# POWER_Management.net
KiCad netlist of a schematic drawn in Altium Designer
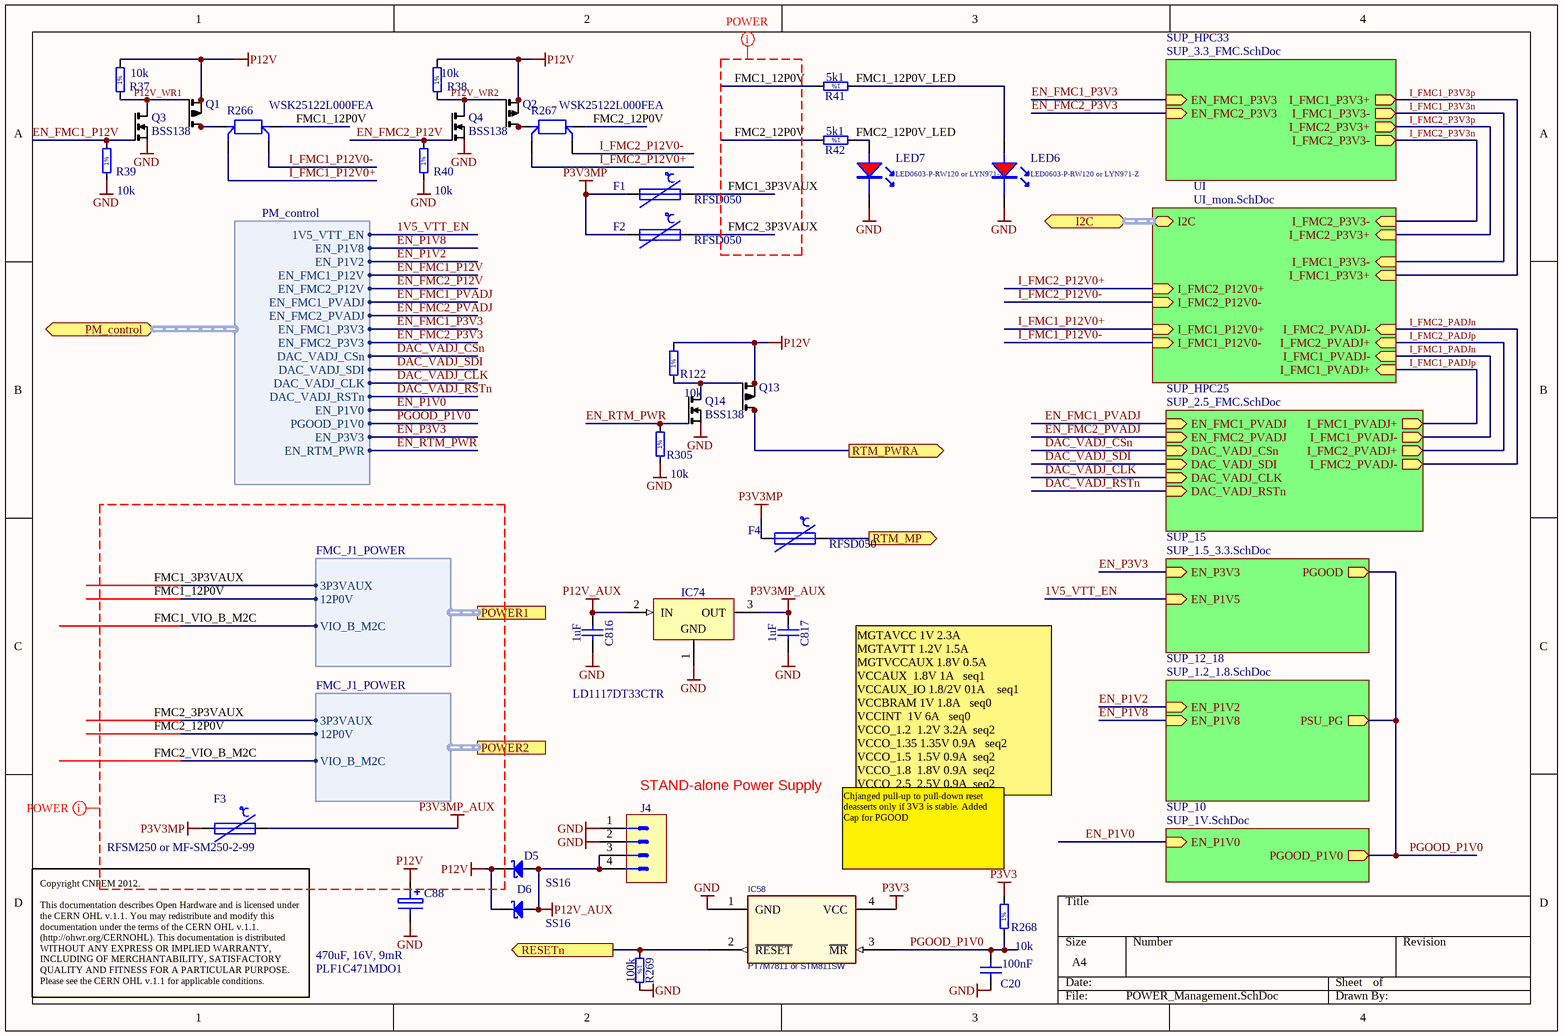
[diagram p0: POWER_Management.SchDoc]

(export (version "E")
  (design (tool "Eeschema 10.0.6"))
  (components
    (comp (ref "C20")
      (value "100nF")
      (footprint "CAPC0603X33N")
      (description "Non-polarised capacitor")
      (fields
        (field (name "PART NUMBER") "CC0201_100NF_6.3V_10%_X5R")
        (field (name "VOLTAGE") "6.3V")
        (field (name "AUTHOR") "CERN DEM JLC")
      )
      (libsource (lib "Capacitors") (part "Capacitor - non polarized"))
    )
    (comp (ref "C88")
      (value "PLF1C471MDO1")
      (footprint "CAPPR500-1000X1250")
      (description "POLY, 470uF, 16V, ESR: 9mR")
      (fields (field (name "ALTIUM_VALUE") "470uF, 16V, 9mR"))
      (libsource (lib "LIBRARY_SCH") (part "CAP_POLYMER_10mm"))
    )
    (comp (ref "C816")
      (value "1uF")
      (footprint "CAPC1608X87N")
      (description "Non-polarised capacitor")
      (fields
        (field (name "PART NUMBER") "CC0603_1UF_16V_10%_X7R")
        (field (name "VOLTAGE") "16V")
        (field (name "AUTHOR") "CERN DEM JLC")
      )
      (libsource (lib "Capacitors") (part "Capacitor - non polarized"))
    )
    (comp (ref "C817")
      (value "1uF")
      (footprint "CAPC1608X87N")
      (description "Non-polarised capacitor")
      (fields
        (field (name "PART NUMBER") "CC0603_1UF_16V_10%_X7R")
        (field (name "VOLTAGE") "16V")
        (field (name "AUTHOR") "CERN DEM JLC")
      )
      (libsource (lib "Capacitors") (part "Capacitor - non polarized"))
    )
    (comp (ref "D5")
      (value "SS16")
      (footprint "DIOM5127X229N")
      (description "Schottky Diode")
      (fields
        (field (name "VOLTAGE") "60V")
        (field (name "POWER") "1A")
        (field (name "AUTHOR") "CERN DEM JLC")
      )
      (libsource (lib "ICs And Semiconductors") (part "Diode Schottky"))
    )
    (comp (ref "D6")
      (value "SS16")
      (footprint "DIOM5127X229N")
      (description "Schottky Diode")
      (fields
        (field (name "VOLTAGE") "60V")
        (field (name "POWER") "1A")
        (field (name "AUTHOR") "CERN DEM JLC")
      )
      (libsource (lib "ICs And Semiconductors") (part "Diode Schottky"))
    )
    (comp (ref "F1")
      (value "RFSD050")
      (footprint "PTC_SMD_1812")
      (description "0.50A/15V")
      (libsource (lib "LIBRARY_SCH") (part "F_PTC_1812"))
    )
    (comp (ref "F2")
      (value "RFSD050")
      (footprint "PTC_SMD_1812")
      (description "0.50A/15V")
      (libsource (lib "LIBRARY_SCH") (part "F_PTC_1812"))
    )
    (comp (ref "F3")
      (value "RFSM250 or MF-SM250-2-99")
      (footprint "SMD150-2")
      (description "2.50A/15V")
      (libsource (lib "LIBRARY_SCH") (part "F_PTC_9.5x6mm"))
    )
    (comp (ref "F4")
      (value "RFSD050")
      (footprint "PTC_SMD_1812")
      (description "0.50A/15V")
      (libsource (lib "LIBRARY_SCH") (part "F_PTC_1812"))
    )
    (comp (ref "IC58")
      (value "PT7M7811 or STM811SW")
      (footprint "SOT143B")
      (description "voltage supervisor")
      (libsource (lib "LIBRARY_SCH") (part "VOLT_STM811"))
    )
    (comp (ref "IC74")
      (value "LD1117DT33CTR")
      (footprint "TO228P972X240-3N-R540X510")
      (description "3-Terminal Regulator 1=GND 2=IN 3=OUT")
      (fields (field (name "MANUFACTURER") "ST MICROELECTRONICS") (field (name "AUTHOR") "CERN DEM JLC"))
      (libsource (lib "ICs And Semiconductors") (part "REG3 1GND-2IN-3OUT"))
    )
    (comp (ref "J4")
      (value "Mini-Fit Jr.™")
      (footprint "MOLEX_39-28-1043")
      (description "Connector 4 Male")
      (fields
        (field (name "PART NUMBER") "MOLEX_39-28-1043")
        (field (name "MANUFACTURER") "MOLEX")
        (field (name "AUTHOR") "CERN DEM JLC")
      )
      (libsource (lib "Connectors") (part "Connector 4 Male"))
    )
    (comp (ref "LED6")
      (value "LED0603-P-RW120 or LYN971-Z")
      (footprint "led_0603R")
      (description "LED 0603 red")
      (libsource (lib "LIBRARY_SCH") (part "LED_0603R"))
    )
    (comp (ref "LED7")
      (value "LED0603-P-RW120 or LYN971-Z")
      (footprint "led_0603R")
      (description "LED 0603 red")
      (libsource (lib "LIBRARY_SCH") (part "LED_0603R"))
    )
    (comp (ref "Q1")
      (value "IRF9317PBF  or IRF9310PbF")
      (footprint "so-8")
      (description "PMOS 30V, 4.6mR, 20A, 2.5W")
      (libsource (lib "LIBRARY_SCH") (part "Q_IRF9310"))
    )
    (comp (ref "Q2")
      (value "IRF9317PBF  or IRF9310PbF")
      (footprint "so-8")
      (description "PMOS 30V, 4.6mR, 20A, 2.5W")
      (libsource (lib "LIBRARY_SCH") (part "Q_IRF9310"))
    )
    (comp (ref "Q3")
      (value "BSS138")
      (footprint "SOT95P251X112-3N")
      (libsource (lib "LIBRARY_SCH") (part "Q_BSS138"))
    )
    (comp (ref "Q4")
      (value "BSS138")
      (footprint "SOT95P251X112-3N")
      (libsource (lib "LIBRARY_SCH") (part "Q_BSS138"))
    )
    (comp (ref "Q13")
      (value "IRF9317PBF  or IRF9310PbF")
      (footprint "so-8")
      (description "PMOS 30V, 4.6mR, 20A, 2.5W")
      (libsource (lib "LIBRARY_SCH") (part "Q_IRF9310"))
    )
    (comp (ref "Q14")
      (value "BSS138")
      (footprint "SOT95P251X112-3N")
      (libsource (lib "LIBRARY_SCH") (part "Q_BSS138"))
    )
    (comp (ref "R37")
      (value "10k")
      (footprint "RESC1005X40N")
      (description "Resistor - 1%")
      (fields
        (field (name "PART NUMBER") "R0402_10K_1%_0.0625W_100PPM")
        (field (name "POWER") "0.0625W")
        (field (name "AUTHOR") "CERN DEM JLC")
      )
      (libsource (lib "Resistors") (part "Resistor - 1%"))
    )
    (comp (ref "R38")
      (value "10k")
      (footprint "RESC1005X40N")
      (description "Resistor - 1%")
      (fields
        (field (name "PART NUMBER") "R0402_10K_1%_0.0625W_100PPM")
        (field (name "POWER") "0.0625W")
        (field (name "AUTHOR") "CERN DEM JLC")
      )
      (libsource (lib "Resistors") (part "Resistor - 1%"))
    )
    (comp (ref "R39")
      (value "10k")
      (footprint "RESC1005X40N")
      (description "Resistor - 1%")
      (fields
        (field (name "PART NUMBER") "R0402_10K_1%_0.0625W_100PPM")
        (field (name "POWER") "0.0625W")
        (field (name "AUTHOR") "CERN DEM JLC")
      )
      (libsource (lib "Resistors") (part "Resistor - 1%"))
    )
    (comp (ref "R40")
      (value "10k")
      (footprint "RESC1005X40N")
      (description "Resistor - 1%")
      (fields
        (field (name "PART NUMBER") "R0402_10K_1%_0.0625W_100PPM")
        (field (name "POWER") "0.0625W")
        (field (name "AUTHOR") "CERN DEM JLC")
      )
      (libsource (lib "Resistors") (part "Resistor - 1%"))
    )
    (comp (ref "R41")
      (value "5k1")
      (footprint "RESC1608X55N")
      (description "Resistor - 1%")
      (fields
        (field (name "PART NUMBER") "R0603_5K1_1%_0.1W_100PPM")
        (field (name "POWER") "0.1W")
        (field (name "AUTHOR") "CERN DEM JLC")
      )
      (libsource (lib "Resistors") (part "Resistor - 1%"))
    )
    (comp (ref "R42")
      (value "5k1")
      (footprint "RESC1608X55N")
      (description "Resistor - 1%")
      (fields
        (field (name "PART NUMBER") "R0603_5K1_1%_0.1W_100PPM")
        (field (name "POWER") "0.1W")
        (field (name "AUTHOR") "CERN DEM JLC")
      )
      (libsource (lib "Resistors") (part "Resistor - 1%"))
    )
    (comp (ref "R122")
      (value "10k")
      (footprint "RESC1005X40N")
      (description "Resistor - 1%")
      (fields
        (field (name "PART NUMBER") "R0402_10K_1%_0.0625W_100PPM")
        (field (name "POWER") "0.0625W")
        (field (name "AUTHOR") "CERN DEM JLC")
      )
      (libsource (lib "Resistors") (part "Resistor - 1%"))
    )
    (comp (ref "R266")
      (value "WSK25122L000FEA")
      (footprint "RES_WSK2512")
      (description "RESISTOR, METAL STRIP, 0.001 OHM 1%")
      (libsource (lib "LIBRARY_SCH") (part "RES_POW_Kelvin"))
    )
    (comp (ref "R267")
      (value "WSK25122L000FEA")
      (footprint "RES_WSK2512")
      (description "RESISTOR, METAL STRIP, 0.001 OHM 1%")
      (libsource (lib "LIBRARY_SCH") (part "RES_POW_Kelvin"))
    )
    (comp (ref "R268")
      (value "10k")
      (footprint "RESC1005X40N")
      (description "Resistor - 1%")
      (fields
        (field (name "PART NUMBER") "R0402_10K_1%_0.0625W_100PPM")
        (field (name "POWER") "0.0625W")
        (field (name "AUTHOR") "CERN DEM JLC")
      )
      (libsource (lib "Resistors") (part "Resistor - 1%"))
    )
    (comp (ref "R269")
      (value "100k")
      (footprint "RESC1005X40N")
      (description "Resistor - 1%")
      (fields
        (field (name "PART NUMBER") "R0402_100K_1%_0.0625W_100PPM")
        (field (name "POWER") "0.0625W")
        (field (name "AUTHOR") "CERN DEM JLC")
      )
      (libsource (lib "Resistors") (part "Resistor - 1%"))
    )
    (comp (ref "R305")
      (value "10k")
      (footprint "RESC1005X40N")
      (description "Resistor - 1%")
      (fields
        (field (name "PART NUMBER") "R0402_10K_1%_0.0625W_100PPM")
        (field (name "POWER") "0.0625W")
        (field (name "AUTHOR") "CERN DEM JLC")
      )
      (libsource (lib "Resistors") (part "Resistor - 1%"))
    )
  )
  (nets
    (net (code "10") (name "/EN_FMC1_P12V") (class "Default")
      (node (ref "Q3") (pin "1") (pinfunction "G_1") (pintype "input"))
      (node (ref "R39") (pin "2") (pinfunction "2_2") (pintype "passive"))
    )
    (net (code "13") (name "/EN_FMC2_P12V") (class "Default")
      (node (ref "Q4") (pin "1") (pinfunction "G_1") (pintype "input"))
      (node (ref "R40") (pin "2") (pinfunction "2_2") (pintype "passive"))
    )
    (net (code "19") (name "/EN_RTM_PWR") (class "Default")
      (node (ref "Q14") (pin "1") (pinfunction "G_1") (pintype "input"))
      (node (ref "R305") (pin "2") (pinfunction "2_2") (pintype "passive"))
    )
    (net (code "20") (name "/FMC1_3P3VAUX") (class "Default")
      (node (ref "F1") (pin "2") (pinfunction "2_2") (pintype "passive"))
    )
    (net (code "21") (name "/FMC1_12P0V") (class "Default")
      (node (ref "R266") (pin "2") (pinfunction "2_2") (pintype "passive"))
      (node (ref "R41") (pin "2") (pinfunction "2_2") (pintype "passive"))
    )
    (net (code "22") (name "/FMC1_12P0V_LED") (class "Default")
      (node (ref "LED6") (pin "A") (pinfunction "A_A") (pintype "passive"))
      (node (ref "R41") (pin "1") (pinfunction "1_1") (pintype "passive"))
    )
    (net (code "24") (name "/FMC2_3P3VAUX") (class "Default")
      (node (ref "F2") (pin "2") (pinfunction "2_2") (pintype "passive"))
    )
    (net (code "25") (name "/FMC2_12P0V") (class "Default")
      (node (ref "R267") (pin "2") (pinfunction "2_2") (pintype "passive"))
      (node (ref "R42") (pin "2") (pinfunction "2_2") (pintype "passive"))
    )
    (net (code "26") (name "/FMC2_12P0V_LED") (class "Default")
      (node (ref "LED7") (pin "A") (pinfunction "A_A") (pintype "passive"))
      (node (ref "R42") (pin "1") (pinfunction "1_1") (pintype "passive"))
    )
    (net (code "31") (name "/I_FMC1_P12V0+") (class "Default")
      (node (ref "R266") (pin "1a") (pinfunction "1a_1a") (pintype "passive"))
    )
    (net (code "32") (name "/I_FMC1_P12V0-") (class "Default")
      (node (ref "R266") (pin "2a") (pinfunction "2a_2a") (pintype "passive"))
    )
    (net (code "37") (name "/I_FMC2_P12V0+") (class "Default")
      (node (ref "R267") (pin "1a") (pinfunction "1a_1a") (pintype "passive"))
    )
    (net (code "38") (name "/I_FMC2_P12V0-") (class "Default")
      (node (ref "R267") (pin "2a") (pinfunction "2a_2a") (pintype "passive"))
    )
    (net (code "41") (name "/P12V_WR1") (class "Default")
      (node (ref "Q1") (pin "4") (pinfunction "G1_4") (pintype "input"))
      (node (ref "Q3") (pin "3") (pinfunction "D_3") (pintype "passive"))
      (node (ref "R37") (pin "1") (pinfunction "1_1") (pintype "passive"))
    )
    (net (code "42") (name "/P12V_WR2") (class "Default")
      (node (ref "Q2") (pin "4") (pinfunction "G1_4") (pintype "input"))
      (node (ref "Q4") (pin "3") (pinfunction "D_3") (pintype "passive"))
      (node (ref "R38") (pin "1") (pinfunction "1_1") (pintype "passive"))
    )
    (net (code "43") (name "/PGOOD_P1V0") (class "Default")
      (node (ref "C20") (pin "1") (pinfunction "1_1") (pintype "passive"))
      (node (ref "IC58") (pin "3") (pinfunction "~{MR}_3") (pintype "input"))
      (node (ref "R268") (pin "1") (pinfunction "1_1") (pintype "passive"))
    )
    (net (code "44") (name "/RESETn") (class "Default")
      (node (ref "IC58") (pin "2") (pinfunction "~{RESET}_2") (pintype "output"))
      (node (ref "R269") (pin "1") (pinfunction "1_1") (pintype "passive"))
    )
    (net (code "45") (name "/RTM_MP") (class "Default")
      (node (ref "F4") (pin "2") (pinfunction "2_2") (pintype "passive"))
    )
    (net (code "46") (name "/RTM_PWRA") (class "Default")
      (node (ref "Q13") (pin "5") (pinfunction "D1_5") (pintype "open_collector"))
      (node (ref "Q13") (pin "6") (pinfunction "D1_6") (pintype "open_collector"))
      (node (ref "Q13") (pin "7") (pinfunction "D1_7") (pintype "open_collector"))
      (node (ref "Q13") (pin "8") (pinfunction "D1_8") (pintype "open_collector"))
    )
    (net (code "49") (name "GND") (class "Default")
      (node (ref "C20") (pin "2") (pinfunction "2_2") (pintype "passive"))
      (node (ref "C816") (pin "2") (pinfunction "2_2") (pintype "passive"))
      (node (ref "C817") (pin "2") (pinfunction "2_2") (pintype "passive"))
      (node (ref "C88") (pin "2") (pinfunction "2_2") (pintype "passive"))
      (node (ref "IC58") (pin "1") (pinfunction "GND_1") (pintype "power_in"))
      (node (ref "IC74") (pin "1") (pinfunction "GND_1") (pintype "power_in"))
      (node (ref "J4") (pin "1") (pinfunction "1_1") (pintype "passive"))
      (node (ref "J4") (pin "2") (pinfunction "2_2") (pintype "passive"))
      (node (ref "LED6") (pin "K") (pinfunction "K_K") (pintype "passive"))
      (node (ref "LED7") (pin "K") (pinfunction "K_K") (pintype "passive"))
      (node (ref "Q14") (pin "2") (pinfunction "S_2") (pintype "passive"))
      (node (ref "Q3") (pin "2") (pinfunction "S_2") (pintype "passive"))
      (node (ref "Q4") (pin "2") (pinfunction "S_2") (pintype "passive"))
      (node (ref "R269") (pin "2") (pinfunction "2_2") (pintype "passive"))
      (node (ref "R305") (pin "1") (pinfunction "1_1") (pintype "passive"))
      (node (ref "R39") (pin "1") (pinfunction "1_1") (pintype "passive"))
      (node (ref "R40") (pin "1") (pinfunction "1_1") (pintype "passive"))
    )
    (net (code "50") (name "Net-(Q1-D1-Pad5)") (class "Default")
      (node (ref "Q1") (pin "5") (pinfunction "D1_5") (pintype "open_collector"))
      (node (ref "Q1") (pin "6") (pinfunction "D1_6") (pintype "open_collector"))
      (node (ref "Q1") (pin "7") (pinfunction "D1_7") (pintype "open_collector"))
      (node (ref "Q1") (pin "8") (pinfunction "D1_8") (pintype "open_collector"))
      (node (ref "R266") (pin "1") (pinfunction "1_1") (pintype "passive"))
    )
    (net (code "51") (name "Net-(Q2-D1-Pad5)") (class "Default")
      (node (ref "Q2") (pin "5") (pinfunction "D1_5") (pintype "open_collector"))
      (node (ref "Q2") (pin "6") (pinfunction "D1_6") (pintype "open_collector"))
      (node (ref "Q2") (pin "7") (pinfunction "D1_7") (pintype "open_collector"))
      (node (ref "Q2") (pin "8") (pinfunction "D1_8") (pintype "open_collector"))
      (node (ref "R267") (pin "1") (pinfunction "1_1") (pintype "passive"))
    )
    (net (code "52") (name "Net-(Q13-G1)") (class "Default")
      (node (ref "Q13") (pin "4") (pinfunction "G1_4") (pintype "input"))
      (node (ref "Q14") (pin "3") (pinfunction "D_3") (pintype "passive"))
      (node (ref "R122") (pin "1") (pinfunction "1_1") (pintype "passive"))
    )
    (net (code "53") (name "P3V3") (class "Default")
      (node (ref "IC58") (pin "4") (pinfunction "VCC_4") (pintype "power_in"))
      (node (ref "R268") (pin "2") (pinfunction "2_2") (pintype "passive"))
    )
    (net (code "54") (name "P3V3MP") (class "Default")
      (node (ref "F1") (pin "1") (pinfunction "1_1") (pintype "passive"))
      (node (ref "F2") (pin "1") (pinfunction "1_1") (pintype "passive"))
      (node (ref "F3") (pin "1") (pinfunction "1_1") (pintype "passive"))
      (node (ref "F4") (pin "1") (pinfunction "1_1") (pintype "passive"))
    )
    (net (code "55") (name "P3V3MP_AUX") (class "Default")
      (node (ref "C817") (pin "1") (pinfunction "1_1") (pintype "passive"))
      (node (ref "F3") (pin "2") (pinfunction "2_2") (pintype "passive"))
      (node (ref "IC74") (pin "3") (pinfunction "OUT_3") (pintype "power_in"))
    )
    (net (code "56") (name "P12V") (class "Default")
      (node (ref "C88") (pin "1") (pinfunction "1_1") (pintype "passive"))
      (node (ref "D5") (pin "1") (pinfunction "C_1") (pintype "passive"))
      (node (ref "D6") (pin "1") (pinfunction "C_1") (pintype "passive"))
      (node (ref "Q1") (pin "1") (pinfunction "S1_1") (pintype "open_emitter"))
      (node (ref "Q1") (pin "2") (pinfunction "S1_2") (pintype "open_emitter"))
      (node (ref "Q1") (pin "3") (pinfunction "S1_3") (pintype "open_emitter"))
      (node (ref "Q13") (pin "1") (pinfunction "S1_1") (pintype "open_emitter"))
      (node (ref "Q13") (pin "2") (pinfunction "S1_2") (pintype "open_emitter"))
      (node (ref "Q13") (pin "3") (pinfunction "S1_3") (pintype "open_emitter"))
      (node (ref "Q2") (pin "1") (pinfunction "S1_1") (pintype "open_emitter"))
      (node (ref "Q2") (pin "2") (pinfunction "S1_2") (pintype "open_emitter"))
      (node (ref "Q2") (pin "3") (pinfunction "S1_3") (pintype "open_emitter"))
      (node (ref "R122") (pin "2") (pinfunction "2_2") (pintype "passive"))
      (node (ref "R37") (pin "2") (pinfunction "2_2") (pintype "passive"))
      (node (ref "R38") (pin "2") (pinfunction "2_2") (pintype "passive"))
    )
    (net (code "57") (name "P12V_AUX") (class "Default")
      (node (ref "C816") (pin "1") (pinfunction "1_1") (pintype "passive"))
      (node (ref "D5") (pin "2") (pinfunction "A_2") (pintype "passive"))
      (node (ref "D6") (pin "2") (pinfunction "A_2") (pintype "passive"))
      (node (ref "IC74") (pin "2") (pinfunction "IN_2") (pintype "input"))
      (node (ref "J4") (pin "3") (pinfunction "3_3") (pintype "passive"))
      (node (ref "J4") (pin "4") (pinfunction "4_4") (pintype "passive"))
    )
  )
)
